# Schematic.net
KiCad netlist of a schematic drawn in EasyEDA
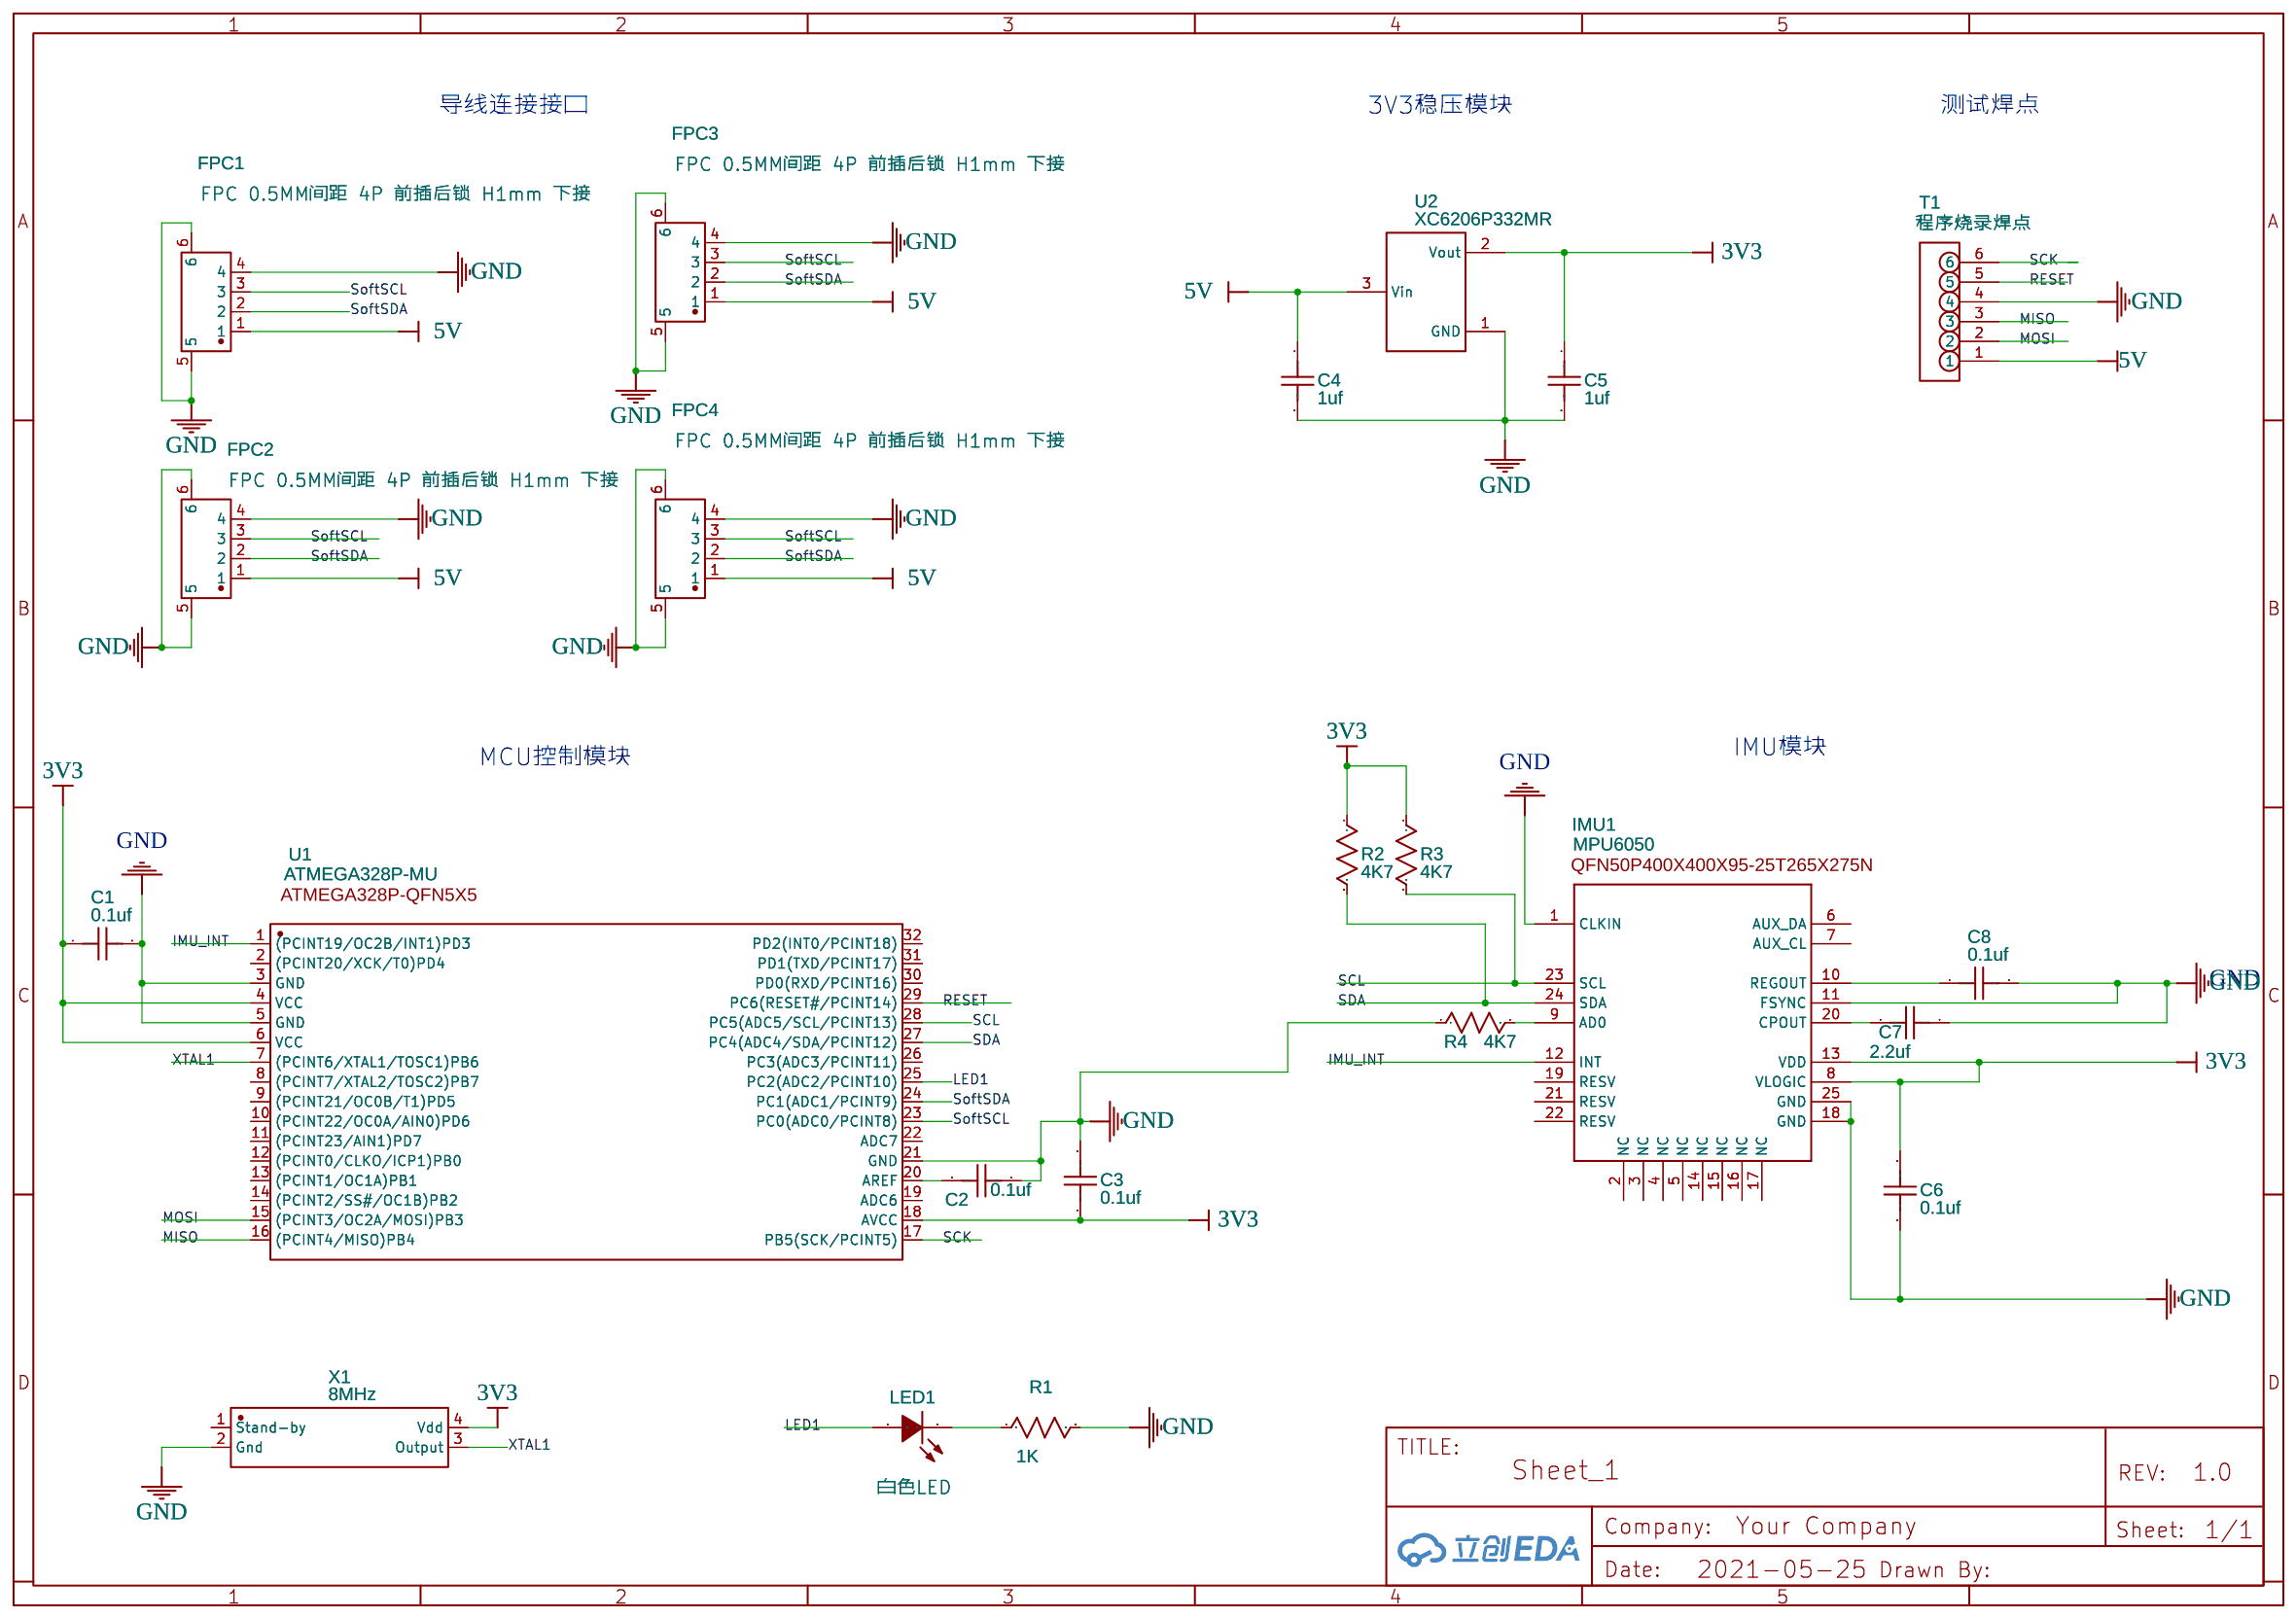
[diagram p0: schematic sheet]

(export (version "E")
  (design (tool "Eeschema 10.0.6"))
  (components
    (comp (ref "C1") (value "0.1uf") (libsource (lib "") (part "C_0402_US")))
    (comp (ref "C2") (value "0.1uf") (libsource (lib "") (part "C_0402_US_2")))
    (comp (ref "C3") (value "0.1uf") (libsource (lib "") (part "C_0402_US_1")))
    (comp (ref "C4") (value "1uf") (libsource (lib "") (part "C_0402_US_3")))
    (comp (ref "C5") (value "1uf") (libsource (lib "") (part "C_0402_US_3")))
    (comp (ref "C6") (value "0.1uf") (libsource (lib "") (part "C_0402_US_3")))
    (comp (ref "C7") (value "2.2uf") (libsource (lib "") (part "C_0402_US_2")))
    (comp (ref "C8") (value "0.1uf") (libsource (lib "") (part "C_0402_US")))
    (comp (ref "FPC1")
      (value "FPC 0.5MM间距 4P 前插后锁 H1mm 下接")
      (fields
        (field (name "BOM_Manufacturer Part") "FPC 0.5MM 4P 翻盖式 H2.0")
        (field (name "BOM_Supplier Part") "C9345")
      )
      (libsource (lib "") (part "FPC 0.5MM 4P 翻盖式 H2.0"))
    )
    (comp (ref "FPC2")
      (value "FPC 0.5MM间距 4P 前插后锁 H1mm 下接")
      (fields
        (field (name "BOM_Manufacturer Part") "FPC 0.5MM 4P 翻盖式 H2.0")
        (field (name "BOM_Supplier Part") "C9345")
      )
      (libsource (lib "") (part "FPC 0.5MM 4P 翻盖式 H2.0"))
    )
    (comp (ref "FPC3")
      (value "FPC 0.5MM间距 4P 前插后锁 H1mm 下接")
      (fields
        (field (name "BOM_Manufacturer Part") "FPC 0.5MM 4P 翻盖式 H2.0")
        (field (name "BOM_Supplier Part") "C9345")
      )
      (libsource (lib "") (part "FPC 0.5MM 4P 翻盖式 H2.0"))
    )
    (comp (ref "FPC4")
      (value "FPC 0.5MM间距 4P 前插后锁 H1mm 下接")
      (fields
        (field (name "BOM_Manufacturer Part") "FPC 0.5MM 4P 翻盖式 H2.0")
        (field (name "BOM_Supplier Part") "C9345")
      )
      (libsource (lib "") (part "FPC 0.5MM 4P 翻盖式 H2.0"))
    )
    (comp (ref "IMU1") (value "MPU6050") (libsource (lib "") (part "MPU6050")))
    (comp (ref "LED1")
      (value "白色LED")
      (fields
        (field (name "BOM_Manufacturer Part") "19-217/BHC-XL2M2TY/3T")
        (field (name "BOM_Supplier Part") "C264464")
      )
      (libsource (lib "") (part "19-217/BHC-XL2M2TY/3T"))
    )
    (comp (ref "R1") (value "1K") (libsource (lib "") (part "R_0402_US_1")))
    (comp (ref "R2") (value "4K7") (libsource (lib "") (part "R_0402_US")))
    (comp (ref "R3") (value "4K7") (libsource (lib "") (part "R_0402_US")))
    (comp (ref "R4") (value "4K7") (libsource (lib "") (part "R_0402_US_1")))
    (comp (ref "T1") (value "程序烧录焊点") (libsource (lib "") (part "Test")))
    (comp (ref "U1")
      (value "ATMEGA328P-MU")
      (fields
        (field (name "BOM_Manufacturer Part") "ATMEGA328P-AU")
        (field (name "BOM_Supplier Part") "C14877")
      )
      (libsource (lib "") (part "ATMEGA328P-AU"))
    )
    (comp (ref "U2")
      (value "XC6206P332MR")
      (fields (field (name "BOM_Supplier Part") "C5446"))
      (libsource (lib "") (part "XC6206P332MR"))
    )
    (comp (ref "X1")
      (value "8MHz")
      (fields
        (field (name "BOM_Manufacturer Part") "ECS-1612MV-080-CN-TR")
        (field (name "BOM_Supplier Part") "C405436")
      )
      (libsource (lib "") (part "ECS-1612MV-080-CN-TR"))
    )
  )
  (nets
    (net (code "1") (name "/IMU_INT") (class "Default")
      (node (ref "IMU1") (pin "12") (pinfunction "INT_12") (pintype "unspecified"))
      (node (ref "U1") (pin "1") (pinfunction "(PCINT19/OC2B/INT1)PD3_1") (pintype "unspecified"))
    )
    (net (code "2") (name "/LED1") (class "Default")
      (node (ref "LED1") (pin "1") (pinfunction "A_1") (pintype "unspecified"))
      (node (ref "U1") (pin "25") (pinfunction "PC2(ADC2/PCINT10)_25") (pintype "unspecified"))
    )
    (net (code "3") (name "/MISO") (class "Default")
      (node (ref "T1") (pin "3") (pinfunction "3_3") (pintype "unspecified"))
      (node (ref "U1") (pin "16") (pinfunction "(PCINT4/MISO)PB4_16") (pintype "unspecified"))
    )
    (net (code "4") (name "/MOSI") (class "Default")
      (node (ref "T1") (pin "2") (pinfunction "2_2") (pintype "unspecified"))
      (node (ref "U1") (pin "15") (pinfunction "(PCINT3/OC2A/MOSI)PB3_15") (pintype "unspecified"))
    )
    (net (code "5") (name "/RESET") (class "Default")
      (node (ref "T1") (pin "5") (pinfunction "5_5") (pintype "unspecified"))
      (node (ref "U1") (pin "29") (pinfunction "PC6(RESET#/PCINT14)_29") (pintype "unspecified"))
    )
    (net (code "6") (name "/SCK") (class "Default")
      (node (ref "T1") (pin "6") (pinfunction "6_6") (pintype "unspecified"))
      (node (ref "U1") (pin "17") (pinfunction "PB5(SCK/PCINT5)_17") (pintype "unspecified"))
    )
    (net (code "7") (name "/SCL") (class "Default")
      (node (ref "IMU1") (pin "23") (pinfunction "SCL_23") (pintype "input"))
      (node (ref "R3") (pin "2") (pinfunction "2_2") (pintype "unspecified"))
      (node (ref "U1") (pin "28") (pinfunction "PC5(ADC5/SCL/PCINT13)_28") (pintype "unspecified"))
    )
    (net (code "8") (name "/SDA") (class "Default")
      (node (ref "IMU1") (pin "24") (pinfunction "SDA_24") (pintype "unspecified"))
      (node (ref "R2") (pin "2") (pinfunction "2_2") (pintype "unspecified"))
      (node (ref "U1") (pin "27") (pinfunction "PC4(ADC4/SDA/PCINT12)_27") (pintype "unspecified"))
    )
    (net (code "9") (name "/SoftSCL") (class "Default")
      (node (ref "FPC1") (pin "3") (pinfunction "3_3") (pintype "unspecified"))
      (node (ref "FPC2") (pin "3") (pinfunction "3_3") (pintype "unspecified"))
      (node (ref "FPC3") (pin "3") (pinfunction "3_3") (pintype "unspecified"))
      (node (ref "FPC4") (pin "3") (pinfunction "3_3") (pintype "unspecified"))
      (node (ref "U1") (pin "23") (pinfunction "PC0(ADC0/PCINT8)_23") (pintype "unspecified"))
    )
    (net (code "10") (name "/SoftSDA") (class "Default")
      (node (ref "FPC1") (pin "2") (pinfunction "2_2") (pintype "unspecified"))
      (node (ref "FPC2") (pin "2") (pinfunction "2_2") (pintype "unspecified"))
      (node (ref "FPC3") (pin "2") (pinfunction "2_2") (pintype "unspecified"))
      (node (ref "FPC4") (pin "2") (pinfunction "2_2") (pintype "unspecified"))
      (node (ref "U1") (pin "24") (pinfunction "PC1(ADC1/PCINT9)_24") (pintype "unspecified"))
    )
    (net (code "11") (name "/XTAL1") (class "Default")
      (node (ref "U1") (pin "7") (pinfunction "(PCINT6/XTAL1/TOSC1)PB6_7") (pintype "unspecified"))
      (node (ref "X1") (pin "3") (pinfunction "Output_3") (pintype "unspecified"))
    )
    (net (code "12") (name "3V3") (class "Default")
      (node (ref "C1") (pin "1") (pinfunction "1_1") (pintype "unspecified"))
      (node (ref "C3") (pin "1") (pinfunction "1_1") (pintype "unspecified"))
      (node (ref "C5") (pin "1") (pinfunction "1_1") (pintype "unspecified"))
      (node (ref "C6") (pin "1") (pinfunction "1_1") (pintype "unspecified"))
      (node (ref "IMU1") (pin "13") (pinfunction "VDD_13") (pintype "passive"))
      (node (ref "IMU1") (pin "8") (pinfunction "VLOGIC_8") (pintype "passive"))
      (node (ref "R2") (pin "1") (pinfunction "1_1") (pintype "unspecified"))
      (node (ref "R3") (pin "1") (pinfunction "1_1") (pintype "unspecified"))
      (node (ref "U1") (pin "18") (pinfunction "AVCC_18") (pintype "unspecified"))
      (node (ref "U1") (pin "4") (pinfunction "VCC_4") (pintype "unspecified"))
      (node (ref "U1") (pin "6") (pinfunction "VCC_6") (pintype "unspecified"))
      (node (ref "U2") (pin "2") (pinfunction "Vout_2") (pintype "unspecified"))
      (node (ref "X1") (pin "4") (pinfunction "Vdd_4") (pintype "unspecified"))
    )
    (net (code "13") (name "5V") (class "Default")
      (node (ref "C4") (pin "1") (pinfunction "1_1") (pintype "unspecified"))
      (node (ref "FPC1") (pin "1") (pinfunction "1_1") (pintype "unspecified"))
      (node (ref "FPC2") (pin "1") (pinfunction "1_1") (pintype "unspecified"))
      (node (ref "FPC3") (pin "1") (pinfunction "1_1") (pintype "unspecified"))
      (node (ref "FPC4") (pin "1") (pinfunction "1_1") (pintype "unspecified"))
      (node (ref "T1") (pin "1") (pinfunction "1_1") (pintype "unspecified"))
      (node (ref "U2") (pin "3") (pinfunction "Vin_3") (pintype "unspecified"))
    )
    (net (code "14") (name "GND") (class "Default")
      (node (ref "C1") (pin "2") (pinfunction "2_2") (pintype "unspecified"))
      (node (ref "C2") (pin "1") (pinfunction "1_1") (pintype "unspecified"))
      (node (ref "C3") (pin "2") (pinfunction "2_2") (pintype "unspecified"))
      (node (ref "C4") (pin "2") (pinfunction "2_2") (pintype "unspecified"))
      (node (ref "C5") (pin "2") (pinfunction "2_2") (pintype "unspecified"))
      (node (ref "C6") (pin "2") (pinfunction "2_2") (pintype "unspecified"))
      (node (ref "C7") (pin "1") (pinfunction "1_1") (pintype "unspecified"))
      (node (ref "C8") (pin "2") (pinfunction "2_2") (pintype "unspecified"))
      (node (ref "FPC1") (pin "4") (pinfunction "4_4") (pintype "unspecified"))
      (node (ref "FPC1") (pin "5") (pinfunction "5_5") (pintype "unspecified"))
      (node (ref "FPC1") (pin "6") (pinfunction "6_6") (pintype "unspecified"))
      (node (ref "FPC2") (pin "4") (pinfunction "4_4") (pintype "unspecified"))
      (node (ref "FPC2") (pin "5") (pinfunction "5_5") (pintype "unspecified"))
      (node (ref "FPC2") (pin "6") (pinfunction "6_6") (pintype "unspecified"))
      (node (ref "FPC3") (pin "4") (pinfunction "4_4") (pintype "unspecified"))
      (node (ref "FPC3") (pin "5") (pinfunction "5_5") (pintype "unspecified"))
      (node (ref "FPC3") (pin "6") (pinfunction "6_6") (pintype "unspecified"))
      (node (ref "FPC4") (pin "4") (pinfunction "4_4") (pintype "unspecified"))
      (node (ref "FPC4") (pin "5") (pinfunction "5_5") (pintype "unspecified"))
      (node (ref "FPC4") (pin "6") (pinfunction "6_6") (pintype "unspecified"))
      (node (ref "IMU1") (pin "1") (pinfunction "CLKIN_1") (pintype "input"))
      (node (ref "IMU1") (pin "11") (pinfunction "FSYNC_11") (pintype "input"))
      (node (ref "IMU1") (pin "18") (pinfunction "GND_18") (pintype "passive"))
      (node (ref "IMU1") (pin "25") (pinfunction "GND_25") (pintype "passive"))
      (node (ref "R1") (pin "2") (pinfunction "2_2") (pintype "unspecified"))
      (node (ref "R4") (pin "1") (pinfunction "1_1") (pintype "unspecified"))
      (node (ref "T1") (pin "4") (pinfunction "4_4") (pintype "unspecified"))
      (node (ref "U1") (pin "21") (pinfunction "GND_21") (pintype "unspecified"))
      (node (ref "U1") (pin "3") (pinfunction "GND_3") (pintype "unspecified"))
      (node (ref "U1") (pin "5") (pinfunction "GND_5") (pintype "unspecified"))
      (node (ref "U2") (pin "1") (pinfunction "GND_1") (pintype "unspecified"))
      (node (ref "X1") (pin "2") (pinfunction "Gnd_2") (pintype "unspecified"))
    )
    (net (code "15") (name "Net-(IMU1-AD0)") (class "Default")
      (node (ref "IMU1") (pin "9") (pinfunction "AD0_9") (pintype "input"))
      (node (ref "R4") (pin "2") (pinfunction "2_2") (pintype "unspecified"))
    )
    (net (code "16") (name "Net-(IMU1-CPOUT)") (class "Default")
      (node (ref "C7") (pin "2") (pinfunction "2_2") (pintype "unspecified"))
      (node (ref "IMU1") (pin "20") (pinfunction "CPOUT_20") (pintype "output"))
    )
    (net (code "17") (name "Net-(IMU1-REGOUT)") (class "Default")
      (node (ref "C8") (pin "1") (pinfunction "1_1") (pintype "unspecified"))
      (node (ref "IMU1") (pin "10") (pinfunction "REGOUT_10") (pintype "output"))
    )
    (net (code "18") (name "Net-(LED1-K)") (class "Default")
      (node (ref "LED1") (pin "2") (pinfunction "K_2") (pintype "unspecified"))
      (node (ref "R1") (pin "1") (pinfunction "1_1") (pintype "unspecified"))
    )
    (net (code "19") (name "Net-(U1-AREF)") (class "Default")
      (node (ref "C2") (pin "2") (pinfunction "2_2") (pintype "unspecified"))
      (node (ref "U1") (pin "20") (pinfunction "AREF_20") (pintype "unspecified"))
    )
    (net (code "20") (name "unconnected-(IMU1-AUX_CL-Pad7)") (class "Default")
      (node (ref "IMU1") (pin "7") (pinfunction "AUX_CL_7") (pintype "unspecified"))
    )
    (net (code "21") (name "unconnected-(IMU1-AUX_DA-Pad6)") (class "Default")
      (node (ref "IMU1") (pin "6") (pinfunction "AUX_DA_6") (pintype "unspecified"))
    )
    (net (code "22") (name "unconnected-(IMU1-NC-Pad2)") (class "Default")
      (node (ref "IMU1") (pin "2") (pinfunction "NC_2") (pintype "unspecified"))
    )
    (net (code "23") (name "unconnected-(IMU1-NC-Pad3)") (class "Default")
      (node (ref "IMU1") (pin "3") (pinfunction "NC_3") (pintype "unspecified"))
    )
    (net (code "24") (name "unconnected-(IMU1-NC-Pad4)") (class "Default")
      (node (ref "IMU1") (pin "4") (pinfunction "NC_4") (pintype "unspecified"))
    )
    (net (code "25") (name "unconnected-(IMU1-NC-Pad5)") (class "Default")
      (node (ref "IMU1") (pin "5") (pinfunction "NC_5") (pintype "unspecified"))
    )
    (net (code "26") (name "unconnected-(IMU1-NC-Pad14)") (class "Default")
      (node (ref "IMU1") (pin "14") (pinfunction "NC_14") (pintype "unspecified"))
    )
    (net (code "27") (name "unconnected-(IMU1-NC-Pad15)") (class "Default")
      (node (ref "IMU1") (pin "15") (pinfunction "NC_15") (pintype "unspecified"))
    )
    (net (code "28") (name "unconnected-(IMU1-NC-Pad16)") (class "Default")
      (node (ref "IMU1") (pin "16") (pinfunction "NC_16") (pintype "unspecified"))
    )
    (net (code "29") (name "unconnected-(IMU1-NC-Pad17)") (class "Default")
      (node (ref "IMU1") (pin "17") (pinfunction "NC_17") (pintype "unspecified"))
    )
    (net (code "30") (name "unconnected-(IMU1-RESV-Pad19)") (class "Default")
      (node (ref "IMU1") (pin "19") (pinfunction "RESV_19") (pintype "unspecified"))
    )
    (net (code "31") (name "unconnected-(IMU1-RESV-Pad21)") (class "Default")
      (node (ref "IMU1") (pin "21") (pinfunction "RESV_21") (pintype "unspecified"))
    )
    (net (code "32") (name "unconnected-(IMU1-RESV-Pad22)") (class "Default")
      (node (ref "IMU1") (pin "22") (pinfunction "RESV_22") (pintype "unspecified"))
    )
    (net (code "33") (name "unconnected-(U1-(PCINT0{slash}CLKO{slash}ICP1)PB0-Pad12)") (class "Default")
      (node (ref "U1") (pin "12") (pinfunction "(PCINT0/CLKO/ICP1)PB0_12") (pintype "unspecified"))
    )
    (net (code "34") (name "unconnected-(U1-(PCINT1{slash}OC1A)PB1-Pad13)") (class "Default")
      (node (ref "U1") (pin "13") (pinfunction "(PCINT1/OC1A)PB1_13") (pintype "unspecified"))
    )
    (net (code "35") (name "unconnected-(U1-(PCINT2{slash}SS#{slash}OC1B)PB2-Pad14)") (class "Default")
      (node (ref "U1") (pin "14") (pinfunction "(PCINT2/SS#/OC1B)PB2_14") (pintype "unspecified"))
    )
    (net (code "36") (name "unconnected-(U1-(PCINT7{slash}XTAL2{slash}TOSC2)PB7-Pad8)") (class "Default")
      (node (ref "U1") (pin "8") (pinfunction "(PCINT7/XTAL2/TOSC2)PB7_8") (pintype "unspecified"))
    )
    (net (code "37") (name "unconnected-(U1-(PCINT20{slash}XCK{slash}T0)PD4-Pad2)") (class "Default")
      (node (ref "U1") (pin "2") (pinfunction "(PCINT20/XCK/T0)PD4_2") (pintype "unspecified"))
    )
    (net (code "38") (name "unconnected-(U1-(PCINT21{slash}OC0B{slash}T1)PD5-Pad9)") (class "Default")
      (node (ref "U1") (pin "9") (pinfunction "(PCINT21/OC0B/T1)PD5_9") (pintype "unspecified"))
    )
    (net (code "39") (name "unconnected-(U1-(PCINT22{slash}OC0A{slash}AIN0)PD6-Pad10)") (class "Default")
      (node (ref "U1") (pin "10") (pinfunction "(PCINT22/OC0A/AIN0)PD6_10") (pintype "unspecified"))
    )
    (net (code "40") (name "unconnected-(U1-(PCINT23{slash}AIN1)PD7-Pad11)") (class "Default")
      (node (ref "U1") (pin "11") (pinfunction "(PCINT23/AIN1)PD7_11") (pintype "unspecified"))
    )
    (net (code "41") (name "unconnected-(U1-ADC6-Pad19)") (class "Default")
      (node (ref "U1") (pin "19") (pinfunction "ADC6_19") (pintype "unspecified"))
    )
    (net (code "42") (name "unconnected-(U1-ADC7-Pad22)") (class "Default")
      (node (ref "U1") (pin "22") (pinfunction "ADC7_22") (pintype "unspecified"))
    )
    (net (code "43") (name "unconnected-(U1-PC3(ADC3{slash}PCINT11)-Pad26)") (class "Default")
      (node (ref "U1") (pin "26") (pinfunction "PC3(ADC3/PCINT11)_26") (pintype "unspecified"))
    )
    (net (code "44") (name "unconnected-(U1-PD0(RXD{slash}PCINT16)-Pad30)") (class "Default")
      (node (ref "U1") (pin "30") (pinfunction "PD0(RXD/PCINT16)_30") (pintype "unspecified"))
    )
    (net (code "45") (name "unconnected-(U1-PD1(TXD{slash}PCINT17)-Pad31)") (class "Default")
      (node (ref "U1") (pin "31") (pinfunction "PD1(TXD/PCINT17)_31") (pintype "unspecified"))
    )
    (net (code "46") (name "unconnected-(U1-PD2(INT0{slash}PCINT18)-Pad32)") (class "Default")
      (node (ref "U1") (pin "32") (pinfunction "PD2(INT0/PCINT18)_32") (pintype "unspecified"))
    )
    (net (code "47") (name "unconnected-(X1-Stand-by-Pad1)") (class "Default")
      (node (ref "X1") (pin "1") (pinfunction "Stand-by_1") (pintype "unspecified"))
    )
  )
)
